# BDAN_CPU.net
KiCad netlist of a schematic drawn in Altium Designer
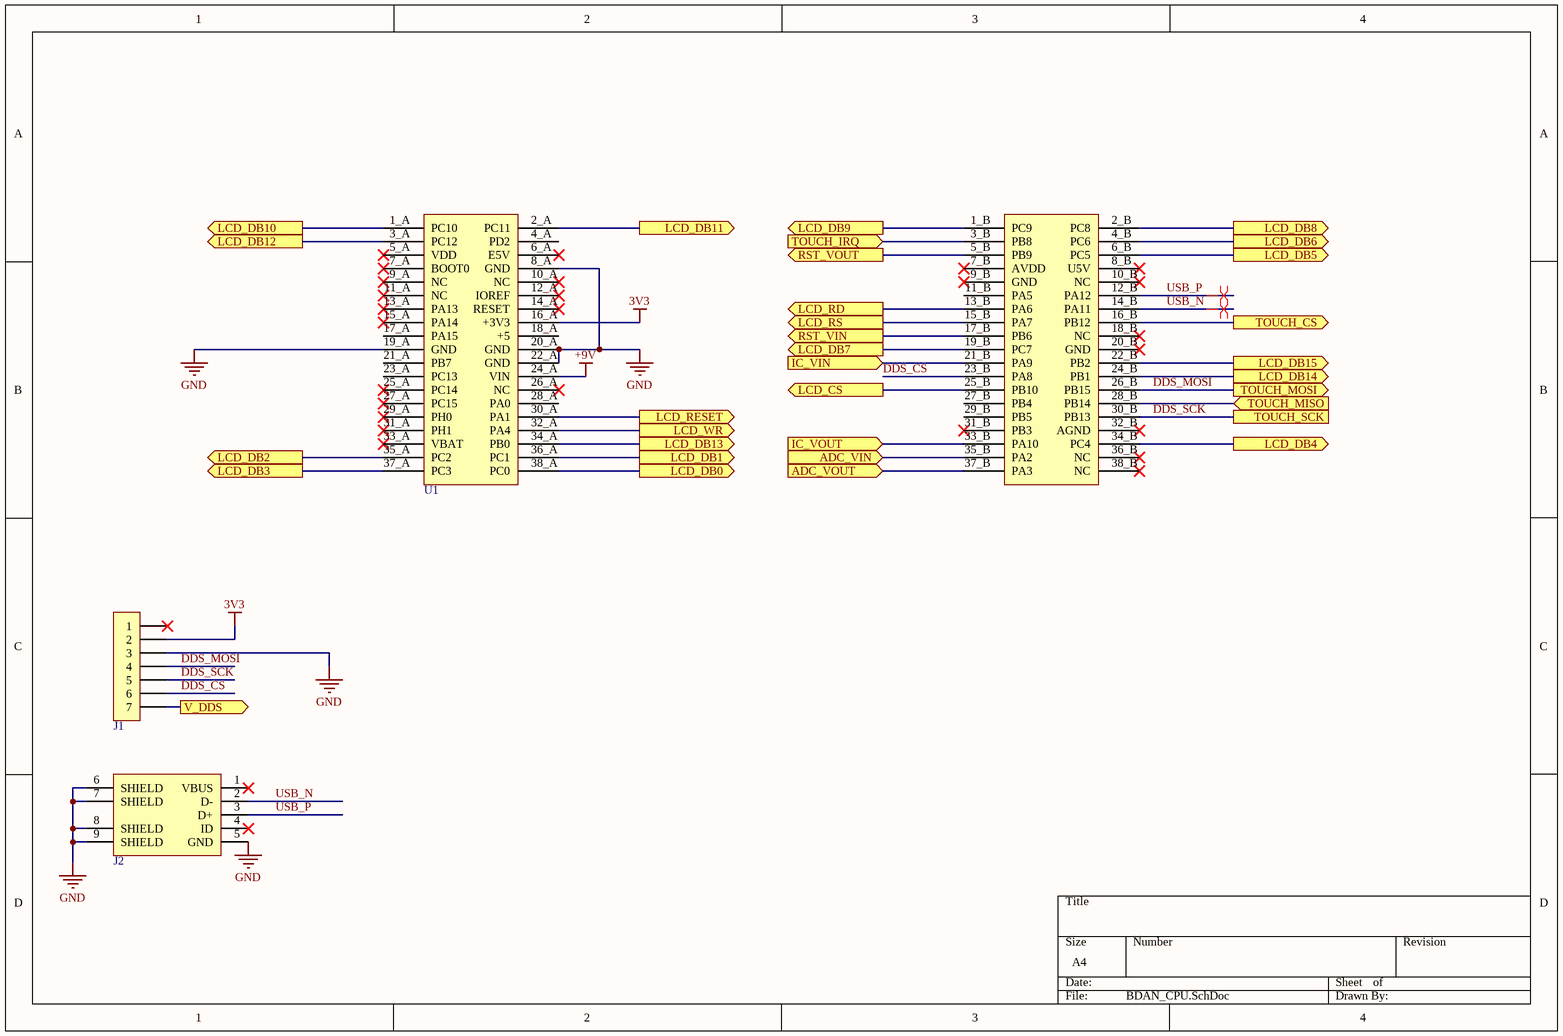
[diagram p0: BDAN_CPU.SchDoc]

(export (version "E")
  (design (tool "Eeschema 10.0.6"))
  (components
    (comp (ref "J1")
      (value "RECEPTACULO 7POS 0.1\"")
      (footprint "SIPF7")
      (description "RECEPTACULO 1x7 POS 0.1\"")
      (fields (field (name "PART NUMBER") "RECEPTACLE_7POS_0.1\""))
      (libsource (lib "gl_LIB") (part "CON7"))
    )
    (comp (ref "J2")
      (value "MINIUSB_FEMALE_SMD")
      (footprint "USB_MINI_FEMALE")
      (description "CONECTOR MINIUSB FEMALE_SMD")
      (fields (field (name "PART NUMBER") "CON_MINIUSB_FEMALE_SMD"))
      (libsource (lib "gl_LIB") (part "CON_MINIUSB_FEMALE"))
    )
    (comp (ref "U1")
      (value "NUCLEO-F401RE")
      (footprint "NUCLEO-F401RE")
      (fields (field (name "MANUFACTURER") "STMicroelectronics"))
      (libsource (lib "gl_LIB") (part "NUCLEO-F401RE"))
    )
  )
  (nets
    (net (code "1") (name "+9V") (class "Default")
      (node (ref "U1") (pin "24_A") (pinfunction "VIN_24_A") (pintype "passive"))
    )
    (net (code "2") (name "/ADC_VIN") (class "Default")
      (node (ref "U1") (pin "35_B") (pinfunction "PA2_35_B") (pintype "passive"))
    )
    (net (code "3") (name "/ADC_VOUT") (class "Default")
      (node (ref "U1") (pin "37_B") (pinfunction "PA3_37_B") (pintype "passive"))
    )
    (net (code "4") (name "/DDS_CS") (class "Default")
      (node (ref "J1") (pin "6") (pinfunction "6_6") (pintype "passive"))
      (node (ref "U1") (pin "23_B") (pinfunction "PA8_23_B") (pintype "passive"))
    )
    (net (code "5") (name "/DDS_MOSI") (class "Default")
      (node (ref "J1") (pin "4") (pinfunction "4_4") (pintype "passive"))
      (node (ref "U1") (pin "26_B") (pinfunction "PB15_26_B") (pintype "passive"))
    )
    (net (code "6") (name "/DDS_SCK") (class "Default")
      (node (ref "J1") (pin "5") (pinfunction "5_5") (pintype "passive"))
      (node (ref "U1") (pin "30_B") (pinfunction "PB13_30_B") (pintype "passive"))
    )
    (net (code "7") (name "/IC_VIN") (class "Default")
      (node (ref "U1") (pin "21_B") (pinfunction "PA9_21_B") (pintype "passive"))
    )
    (net (code "8") (name "/IC_VOUT") (class "Default")
      (node (ref "U1") (pin "33_B") (pinfunction "PA10_33_B") (pintype "passive"))
    )
    (net (code "9") (name "/LCD_CS") (class "Default")
      (node (ref "U1") (pin "25_B") (pinfunction "PB10_25_B") (pintype "passive"))
    )
    (net (code "10") (name "/LCD_DB0") (class "Default")
      (node (ref "U1") (pin "38_A") (pinfunction "PC0_38_A") (pintype "passive"))
    )
    (net (code "11") (name "/LCD_DB1") (class "Default")
      (node (ref "U1") (pin "36_A") (pinfunction "PC1_36_A") (pintype "passive"))
    )
    (net (code "12") (name "/LCD_DB2") (class "Default")
      (node (ref "U1") (pin "35_A") (pinfunction "PC2_35_A") (pintype "passive"))
    )
    (net (code "13") (name "/LCD_DB3") (class "Default")
      (node (ref "U1") (pin "37_A") (pinfunction "PC3_37_A") (pintype "passive"))
    )
    (net (code "14") (name "/LCD_DB4") (class "Default")
      (node (ref "U1") (pin "34_B") (pinfunction "PC4_34_B") (pintype "passive"))
    )
    (net (code "15") (name "/LCD_DB5") (class "Default")
      (node (ref "U1") (pin "6_B") (pinfunction "PC5_6_B") (pintype "passive"))
    )
    (net (code "16") (name "/LCD_DB6") (class "Default")
      (node (ref "U1") (pin "4_B") (pinfunction "PC6_4_B") (pintype "passive"))
    )
    (net (code "17") (name "/LCD_DB7") (class "Default")
      (node (ref "U1") (pin "19_B") (pinfunction "PC7_19_B") (pintype "passive"))
    )
    (net (code "18") (name "/LCD_DB8") (class "Default")
      (node (ref "U1") (pin "2_B") (pinfunction "PC8_2_B") (pintype "passive"))
    )
    (net (code "19") (name "/LCD_DB9") (class "Default")
      (node (ref "U1") (pin "1_B") (pinfunction "PC9_1_B") (pintype "passive"))
    )
    (net (code "20") (name "/LCD_DB10") (class "Default")
      (node (ref "U1") (pin "1_A") (pinfunction "PC10_1_A") (pintype "passive"))
    )
    (net (code "21") (name "/LCD_DB11") (class "Default")
      (node (ref "U1") (pin "2_A") (pinfunction "PC11_2_A") (pintype "passive"))
    )
    (net (code "22") (name "/LCD_DB12") (class "Default")
      (node (ref "U1") (pin "3_A") (pinfunction "PC12_3_A") (pintype "passive"))
    )
    (net (code "23") (name "/LCD_DB13") (class "Default")
      (node (ref "U1") (pin "34_A") (pinfunction "PB0_34_A") (pintype "passive"))
    )
    (net (code "24") (name "/LCD_DB14") (class "Default")
      (node (ref "U1") (pin "24_B") (pinfunction "PB1_24_B") (pintype "passive"))
    )
    (net (code "25") (name "/LCD_DB15") (class "Default")
      (node (ref "U1") (pin "22_B") (pinfunction "PB2_22_B") (pintype "passive"))
    )
    (net (code "26") (name "/LCD_RD") (class "Default")
      (node (ref "U1") (pin "13_B") (pinfunction "PA6_13_B") (pintype "passive"))
    )
    (net (code "27") (name "/LCD_RESET") (class "Default")
      (node (ref "U1") (pin "30_A") (pinfunction "PA1_30_A") (pintype "passive"))
    )
    (net (code "28") (name "/LCD_RS") (class "Default")
      (node (ref "U1") (pin "15_B") (pinfunction "PA7_15_B") (pintype "passive"))
    )
    (net (code "29") (name "/LCD_WR") (class "Default")
      (node (ref "U1") (pin "32_A") (pinfunction "PA4_32_A") (pintype "passive"))
    )
    (net (code "30") (name "/RST_VIN") (class "Default")
      (node (ref "U1") (pin "17_B") (pinfunction "PB6_17_B") (pintype "passive"))
    )
    (net (code "31") (name "/RST_VOUT") (class "Default")
      (node (ref "U1") (pin "5_B") (pinfunction "PB9_5_B") (pintype "passive"))
    )
    (net (code "32") (name "/TOUCH_CS") (class "Default")
      (node (ref "U1") (pin "16_B") (pinfunction "PB12_16_B") (pintype "passive"))
    )
    (net (code "33") (name "/TOUCH_IRQ") (class "Default")
      (node (ref "U1") (pin "3_B") (pinfunction "PB8_3_B") (pintype "passive"))
    )
    (net (code "34") (name "/TOUCH_MISO") (class "Default")
      (node (ref "U1") (pin "28_B") (pinfunction "PB14_28_B") (pintype "passive"))
    )
    (net (code "35") (name "/USB_N") (class "Default")
      (node (ref "J2") (pin "2") (pinfunction "D-_2") (pintype "passive"))
      (node (ref "U1") (pin "14_B") (pinfunction "PA11_14_B") (pintype "passive"))
    )
    (net (code "36") (name "/USB_P") (class "Default")
      (node (ref "J2") (pin "3") (pinfunction "D+_3") (pintype "passive"))
      (node (ref "U1") (pin "12_B") (pinfunction "PA12_12_B") (pintype "passive"))
    )
    (net (code "37") (name "/V_DDS") (class "Default")
      (node (ref "J1") (pin "7") (pinfunction "7_7") (pintype "passive"))
    )
    (net (code "38") (name "3V3") (class "Default")
      (node (ref "J1") (pin "2") (pinfunction "2_2") (pintype "passive"))
      (node (ref "U1") (pin "16_A") (pinfunction "+3V3_16_A") (pintype "passive"))
    )
    (net (code "39") (name "GND") (class "Default")
      (node (ref "J1") (pin "3") (pinfunction "3_3") (pintype "passive"))
      (node (ref "J2") (pin "5") (pinfunction "GND_5") (pintype "passive"))
      (node (ref "J2") (pin "6") (pinfunction "SHIELD_6") (pintype "passive"))
      (node (ref "J2") (pin "7") (pinfunction "SHIELD_7") (pintype "passive"))
      (node (ref "J2") (pin "8") (pinfunction "SHIELD_8") (pintype "passive"))
      (node (ref "J2") (pin "9") (pinfunction "SHIELD_9") (pintype "passive"))
      (node (ref "U1") (pin "19_A") (pinfunction "GND_19_A") (pintype "passive"))
      (node (ref "U1") (pin "20_A") (pinfunction "GND_20_A") (pintype "passive"))
      (node (ref "U1") (pin "22_A") (pinfunction "GND_22_A") (pintype "passive"))
      (node (ref "U1") (pin "8_A") (pinfunction "GND_8_A") (pintype "passive"))
    )
    (net (code "40") (name "unconnected-(J1-Pad1)") (class "Default")
      (node (ref "J1") (pin "1") (pinfunction "1_1") (pintype "passive+no_connect"))
    )
    (net (code "41") (name "unconnected-(J2-ID-Pad4)") (class "Default")
      (node (ref "J2") (pin "4") (pinfunction "ID_4") (pintype "passive+no_connect"))
    )
    (net (code "42") (name "unconnected-(J2-VBUS-Pad1)") (class "Default")
      (node (ref "J2") (pin "1") (pinfunction "VBUS_1") (pintype "passive+no_connect"))
    )
    (net (code "43") (name "unconnected-(U1-+5-Pad18_A)") (class "Default")
      (node (ref "U1") (pin "18_A") (pinfunction "+5_18_A") (pintype "passive"))
    )
    (net (code "44") (name "unconnected-(U1-AGND-Pad32_B)") (class "Default")
      (node (ref "U1") (pin "32_B") (pinfunction "AGND_32_B") (pintype "passive+no_connect"))
    )
    (net (code "45") (name "unconnected-(U1-AVDD-Pad7_B)") (class "Default")
      (node (ref "U1") (pin "7_B") (pinfunction "AVDD_7_B") (pintype "passive+no_connect"))
    )
    (net (code "46") (name "unconnected-(U1-BOOT0-Pad7_A)") (class "Default")
      (node (ref "U1") (pin "7_A") (pinfunction "BOOT0_7_A") (pintype "passive+no_connect"))
    )
    (net (code "47") (name "unconnected-(U1-E5V-Pad6_A)") (class "Default")
      (node (ref "U1") (pin "6_A") (pinfunction "E5V_6_A") (pintype "passive+no_connect"))
    )
    (net (code "48") (name "unconnected-(U1-GND-Pad9_B)") (class "Default")
      (node (ref "U1") (pin "9_B") (pinfunction "GND_9_B") (pintype "passive+no_connect"))
    )
    (net (code "49") (name "unconnected-(U1-GND-Pad20_B)") (class "Default")
      (node (ref "U1") (pin "20_B") (pinfunction "GND_20_B") (pintype "passive+no_connect"))
    )
    (net (code "50") (name "unconnected-(U1-IOREF-Pad12_A)") (class "Default")
      (node (ref "U1") (pin "12_A") (pinfunction "IOREF_12_A") (pintype "passive+no_connect"))
    )
    (net (code "51") (name "unconnected-(U1-NC-Pad9_A)") (class "Default")
      (node (ref "U1") (pin "9_A") (pinfunction "NC_9_A") (pintype "passive+no_connect"))
    )
    (net (code "52") (name "unconnected-(U1-NC-Pad10_A)") (class "Default")
      (node (ref "U1") (pin "10_A") (pinfunction "NC_10_A") (pintype "passive+no_connect"))
    )
    (net (code "53") (name "unconnected-(U1-NC-Pad10_B)") (class "Default")
      (node (ref "U1") (pin "10_B") (pinfunction "NC_10_B") (pintype "passive+no_connect"))
    )
    (net (code "54") (name "unconnected-(U1-NC-Pad11_A)") (class "Default")
      (node (ref "U1") (pin "11_A") (pinfunction "NC_11_A") (pintype "passive+no_connect"))
    )
    (net (code "55") (name "unconnected-(U1-NC-Pad18_B)") (class "Default")
      (node (ref "U1") (pin "18_B") (pinfunction "NC_18_B") (pintype "passive+no_connect"))
    )
    (net (code "56") (name "unconnected-(U1-NC-Pad26_A)") (class "Default")
      (node (ref "U1") (pin "26_A") (pinfunction "NC_26_A") (pintype "passive+no_connect"))
    )
    (net (code "57") (name "unconnected-(U1-NC-Pad36_B)") (class "Default")
      (node (ref "U1") (pin "36_B") (pinfunction "NC_36_B") (pintype "passive+no_connect"))
    )
    (net (code "58") (name "unconnected-(U1-NC-Pad38_B)") (class "Default")
      (node (ref "U1") (pin "38_B") (pinfunction "NC_38_B") (pintype "passive+no_connect"))
    )
    (net (code "59") (name "unconnected-(U1-PA0-Pad28_A)") (class "Default")
      (node (ref "U1") (pin "28_A") (pinfunction "PA0_28_A") (pintype "passive"))
    )
    (net (code "60") (name "unconnected-(U1-PA5-Pad11_B)") (class "Default")
      (node (ref "U1") (pin "11_B") (pinfunction "PA5_11_B") (pintype "passive"))
    )
    (net (code "61") (name "unconnected-(U1-PA13-Pad13_A)") (class "Default")
      (node (ref "U1") (pin "13_A") (pinfunction "PA13_13_A") (pintype "passive+no_connect"))
    )
    (net (code "62") (name "unconnected-(U1-PA14-Pad15_A)") (class "Default")
      (node (ref "U1") (pin "15_A") (pinfunction "PA14_15_A") (pintype "passive+no_connect"))
    )
    (net (code "63") (name "unconnected-(U1-PA15-Pad17_A)") (class "Default")
      (node (ref "U1") (pin "17_A") (pinfunction "PA15_17_A") (pintype "passive"))
    )
    (net (code "64") (name "unconnected-(U1-PB3-Pad31_B)") (class "Default")
      (node (ref "U1") (pin "31_B") (pinfunction "PB3_31_B") (pintype "passive+no_connect"))
    )
    (net (code "65") (name "unconnected-(U1-PB4-Pad27_B)") (class "Default")
      (node (ref "U1") (pin "27_B") (pinfunction "PB4_27_B") (pintype "passive"))
    )
    (net (code "66") (name "unconnected-(U1-PB5-Pad29_B)") (class "Default")
      (node (ref "U1") (pin "29_B") (pinfunction "PB5_29_B") (pintype "passive"))
    )
    (net (code "67") (name "unconnected-(U1-PB7-Pad21_A)") (class "Default")
      (node (ref "U1") (pin "21_A") (pinfunction "PB7_21_A") (pintype "passive"))
    )
    (net (code "68") (name "unconnected-(U1-PC13-Pad23_A)") (class "Default")
      (node (ref "U1") (pin "23_A") (pinfunction "PC13_23_A") (pintype "passive"))
    )
    (net (code "69") (name "unconnected-(U1-PC14-Pad25_A)") (class "Default")
      (node (ref "U1") (pin "25_A") (pinfunction "PC14_25_A") (pintype "passive+no_connect"))
    )
    (net (code "70") (name "unconnected-(U1-PC15-Pad27_A)") (class "Default")
      (node (ref "U1") (pin "27_A") (pinfunction "PC15_27_A") (pintype "passive+no_connect"))
    )
    (net (code "71") (name "unconnected-(U1-PD2-Pad4_A)") (class "Default")
      (node (ref "U1") (pin "4_A") (pinfunction "PD2_4_A") (pintype "passive"))
    )
    (net (code "72") (name "unconnected-(U1-PH0-Pad29_A)") (class "Default")
      (node (ref "U1") (pin "29_A") (pinfunction "PH0_29_A") (pintype "passive+no_connect"))
    )
    (net (code "73") (name "unconnected-(U1-PH1-Pad31_A)") (class "Default")
      (node (ref "U1") (pin "31_A") (pinfunction "PH1_31_A") (pintype "passive+no_connect"))
    )
    (net (code "74") (name "unconnected-(U1-RESET-Pad14_A)") (class "Default")
      (node (ref "U1") (pin "14_A") (pinfunction "RESET_14_A") (pintype "passive+no_connect"))
    )
    (net (code "75") (name "unconnected-(U1-U5V-Pad8_B)") (class "Default")
      (node (ref "U1") (pin "8_B") (pinfunction "U5V_8_B") (pintype "passive+no_connect"))
    )
    (net (code "76") (name "unconnected-(U1-VBAT-Pad33_A)") (class "Default")
      (node (ref "U1") (pin "33_A") (pinfunction "VBAT_33_A") (pintype "passive+no_connect"))
    )
    (net (code "77") (name "unconnected-(U1-VDD-Pad5_A)") (class "Default")
      (node (ref "U1") (pin "5_A") (pinfunction "VDD_5_A") (pintype "passive+no_connect"))
    )
  )
)
